# BuzzerCircuit.net
KiCad netlist of a schematic drawn in Altium Designer
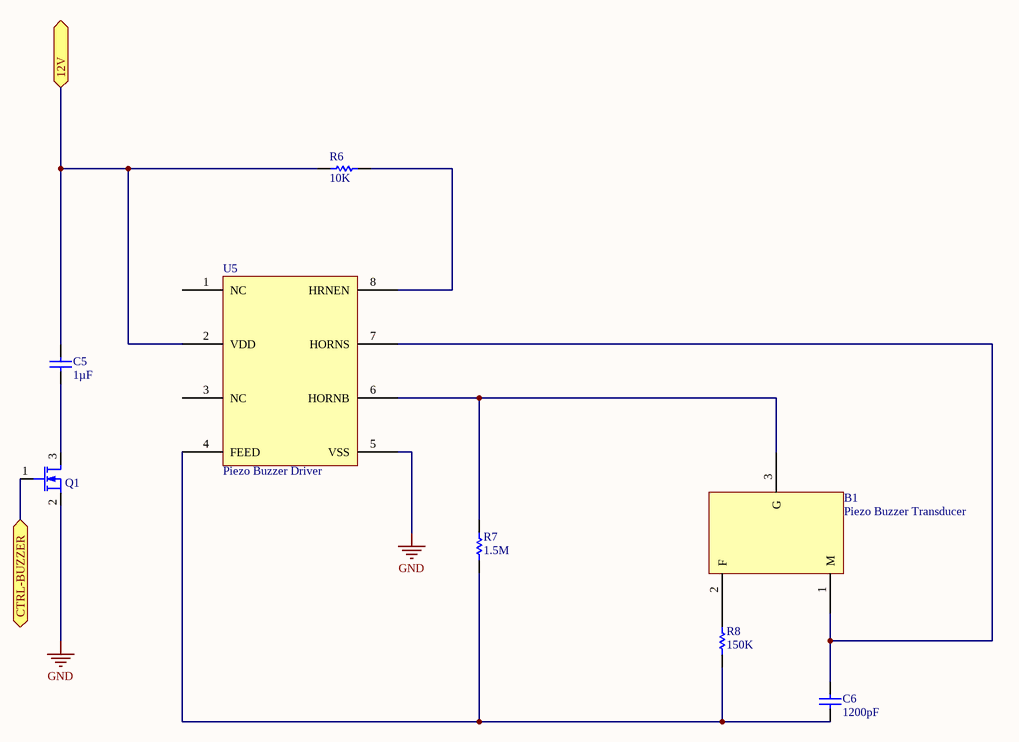
[diagram p0: BuzzerCircuit.SchDoc]

(export (version "E")
  (design (tool "Eeschema 10.0.6"))
  (components
    (comp (ref "B1")
      (value "Piezo Buzzer Transducer")
      (footprint "2017 Buzzer")
      (libsource (lib "DashComponentsLib") (part "Piezo Buzzer Transducer"))
    )
    (comp (ref "C5")
      (value "1µF")
      (footprint "0603")
      (description "Capacitor")
      (fields (field (name "PUBLISHER") "Altium Limited"))
      (libsource (lib "Miscellaneous Devices") (part "Cap"))
    )
    (comp (ref "C6")
      (value "1200pF")
      (footprint "0603")
      (description "Capacitor")
      (fields (field (name "PUBLISHER") "Altium Limited"))
      (libsource (lib "Miscellaneous Devices") (part "Cap"))
    )
    (comp (ref "Q1")
      (value "NMOS - MTM232270LBF")
      (footprint "MTM232270LBF")
      (libsource (lib "UVICHybridLibrary") (part "NMOS - MTM232270LBF"))
    )
    (comp (ref "R6")
      (value "10K")
      (footprint "0603")
      (description "Resistor")
      (fields (field (name "PUBLISHER") "Altium Limited"))
      (libsource (lib "Miscellaneous Devices") (part "Res1"))
    )
    (comp (ref "R7")
      (value "1.5M")
      (footprint "0603")
      (description "Resistor")
      (fields (field (name "PUBLISHER") "Altium Limited"))
      (libsource (lib "Miscellaneous Devices") (part "Res1"))
    )
    (comp (ref "R8")
      (value "150K")
      (footprint "0603")
      (description "Resistor")
      (fields (field (name "PUBLISHER") "Altium Limited"))
      (libsource (lib "Miscellaneous Devices") (part "Res1"))
    )
    (comp (ref "U5")
      (value "Piezo Buzzer Driver")
      (footprint "Buzzer Driver")
      (libsource (lib "DashComponentsLib") (part "Piezo Buzzer Driver"))
    )
  )
  (nets
    (net (code "1") (name "/12V") (class "Default")
      (node (ref "C5") (pin "2") (pinfunction "2_2") (pintype "passive"))
      (node (ref "R6") (pin "1") (pinfunction "1_1") (pintype "passive"))
      (node (ref "U5") (pin "2") (pinfunction "VDD_2") (pintype "passive"))
    )
    (net (code "2") (name "/CTRL-BUZZER") (class "Default")
      (node (ref "Q1") (pin "1") (pinfunction "1_1") (pintype "passive"))
    )
    (net (code "3") (name "GND") (class "Default")
      (node (ref "Q1") (pin "2") (pinfunction "2_2") (pintype "passive"))
      (node (ref "U5") (pin "5") (pinfunction "VSS_5") (pintype "passive"))
    )
    (net (code "4") (name "Net-(B1-F)") (class "Default")
      (node (ref "B1") (pin "2") (pinfunction "F_2") (pintype "passive"))
      (node (ref "R8") (pin "2") (pinfunction "2_2") (pintype "passive"))
    )
    (net (code "5") (name "Net-(B1-G)") (class "Default")
      (node (ref "B1") (pin "3") (pinfunction "G_3") (pintype "passive"))
      (node (ref "R7") (pin "2") (pinfunction "2_2") (pintype "passive"))
      (node (ref "U5") (pin "6") (pinfunction "HORNB_6") (pintype "passive"))
    )
    (net (code "6") (name "Net-(B1-M)") (class "Default")
      (node (ref "B1") (pin "1") (pinfunction "M_1") (pintype "passive"))
      (node (ref "C6") (pin "2") (pinfunction "2_2") (pintype "passive"))
      (node (ref "U5") (pin "7") (pinfunction "HORNS_7") (pintype "passive"))
    )
    (net (code "7") (name "Net-(C5-Pad1)") (class "Default")
      (node (ref "C5") (pin "1") (pinfunction "1_1") (pintype "passive"))
      (node (ref "Q1") (pin "3") (pinfunction "3_3") (pintype "passive"))
    )
    (net (code "8") (name "Net-(U5-FEED)") (class "Default")
      (node (ref "C6") (pin "1") (pinfunction "1_1") (pintype "passive"))
      (node (ref "R7") (pin "1") (pinfunction "1_1") (pintype "passive"))
      (node (ref "R8") (pin "1") (pinfunction "1_1") (pintype "passive"))
      (node (ref "U5") (pin "4") (pinfunction "FEED_4") (pintype "passive"))
    )
    (net (code "9") (name "Net-(U5-HRNEN)") (class "Default")
      (node (ref "R6") (pin "2") (pinfunction "2_2") (pintype "passive"))
      (node (ref "U5") (pin "8") (pinfunction "HRNEN_8") (pintype "passive"))
    )
    (net (code "10") (name "unconnected-(U5-NC-Pad1)") (class "Default")
      (node (ref "U5") (pin "1") (pinfunction "NC_1") (pintype "passive"))
    )
    (net (code "11") (name "unconnected-(U5-NC-Pad3)") (class "Default")
      (node (ref "U5") (pin "3") (pinfunction "NC_3") (pintype "passive"))
    )
  )
)
